# Basic_Logic_gates.net
KiCad netlist of a schematic drawn in Altium Designer
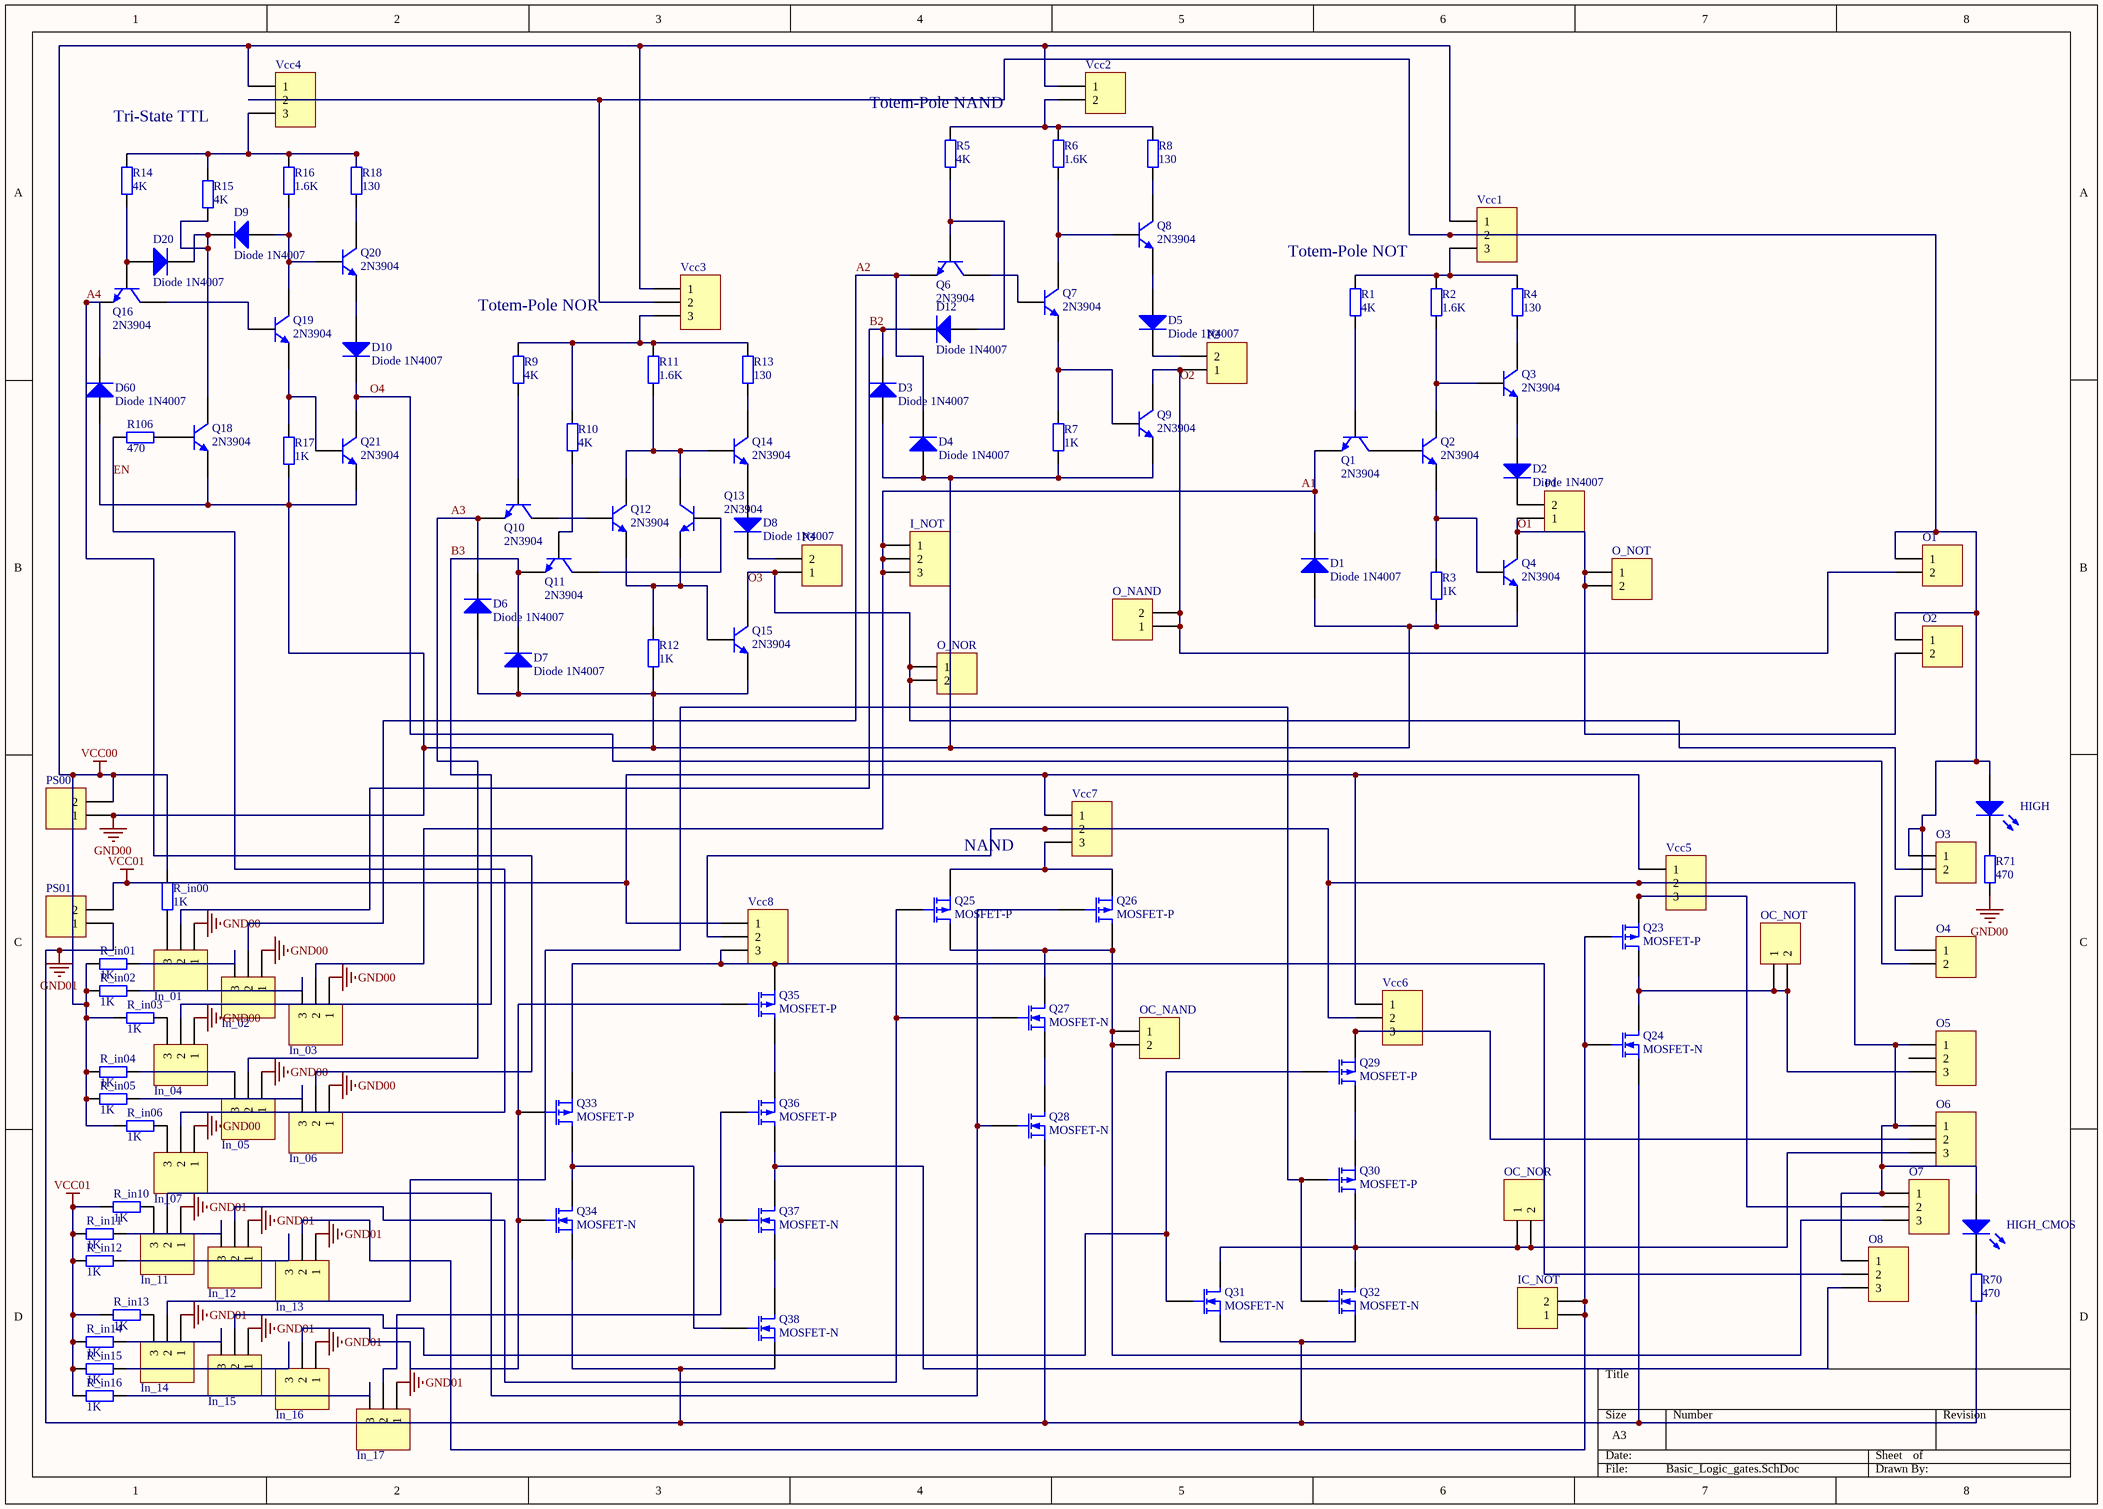
[diagram p0: Basic_Logic_gates.SchDoc]

(export (version "E")
  (design (tool "Eeschema 10.0.6"))
  (components
    (comp (ref "D1")
      (value "Diode 1N4007")
      (footprint "DO-41")
      (description "1 Amp General Purpose Rectifier")
      (libsource (lib "Miscellaneous Devices") (part "Diode 1N4007"))
    )
    (comp (ref "D2")
      (value "Diode 1N4007")
      (footprint "DO-41")
      (description "1 Amp General Purpose Rectifier")
      (libsource (lib "Miscellaneous Devices") (part "Diode 1N4007"))
    )
    (comp (ref "D3")
      (value "Diode 1N4007")
      (footprint "DO-41")
      (description "1 Amp General Purpose Rectifier")
      (libsource (lib "Miscellaneous Devices") (part "Diode 1N4007"))
    )
    (comp (ref "D4")
      (value "Diode 1N4007")
      (footprint "DO-41")
      (description "1 Amp General Purpose Rectifier")
      (libsource (lib "Miscellaneous Devices") (part "Diode 1N4007"))
    )
    (comp (ref "D5")
      (value "Diode 1N4007")
      (footprint "DO-41")
      (description "1 Amp General Purpose Rectifier")
      (libsource (lib "Miscellaneous Devices") (part "Diode 1N4007"))
    )
    (comp (ref "D6")
      (value "Diode 1N4007")
      (footprint "DO-41")
      (description "1 Amp General Purpose Rectifier")
      (libsource (lib "Miscellaneous Devices") (part "Diode 1N4007"))
    )
    (comp (ref "D7")
      (value "Diode 1N4007")
      (footprint "DO-41")
      (description "1 Amp General Purpose Rectifier")
      (libsource (lib "Miscellaneous Devices") (part "Diode 1N4007"))
    )
    (comp (ref "D8")
      (value "Diode 1N4007")
      (footprint "DO-41")
      (description "1 Amp General Purpose Rectifier")
      (libsource (lib "Miscellaneous Devices") (part "Diode 1N4007"))
    )
    (comp (ref "D9")
      (value "Diode 1N4007")
      (footprint "DO-41")
      (description "1 Amp General Purpose Rectifier")
      (libsource (lib "Miscellaneous Devices") (part "Diode 1N4007"))
    )
    (comp (ref "D10")
      (value "Diode 1N4007")
      (footprint "DO-41")
      (description "1 Amp General Purpose Rectifier")
      (libsource (lib "Miscellaneous Devices") (part "Diode 1N4007"))
    )
    (comp (ref "D12")
      (value "Diode 1N4007")
      (footprint "DO-41")
      (description "1 Amp General Purpose Rectifier")
      (libsource (lib "Miscellaneous Devices") (part "Diode 1N4007"))
    )
    (comp (ref "D20")
      (value "Diode 1N4007")
      (footprint "DO-41")
      (description "1 Amp General Purpose Rectifier")
      (libsource (lib "Miscellaneous Devices") (part "Diode 1N4007"))
    )
    (comp (ref "D60")
      (value "Diode 1N4007")
      (footprint "DO-41")
      (description "1 Amp General Purpose Rectifier")
      (libsource (lib "Miscellaneous Devices") (part "Diode 1N4007"))
    )
    (comp (ref "HIGH")
      (value "LED0")
      (footprint "LED-0")
      (description "Typical INFRARED GaAs LED")
      (libsource (lib "Miscellaneous Devices") (part "LED0"))
    )
    (comp (ref "HIGH_CMOS")
      (value "LED0")
      (footprint "LED-0")
      (description "Typical INFRARED GaAs LED")
      (libsource (lib "Miscellaneous Devices") (part "LED0"))
    )
    (comp (ref "IC_NOT")
      (value "Header 2")
      (footprint "HDR1X2")
      (description "Header, 2-Pin")
      (libsource (lib "Miscellaneous Connectors") (part "Header 2"))
    )
    (comp (ref "In_01")
      (value "Header 3")
      (footprint "HDR1X3")
      (description "Header, 3-Pin")
      (libsource (lib "") (part "Header 3_1"))
    )
    (comp (ref "In_02")
      (value "Header 3")
      (footprint "HDR1X3")
      (description "Header, 3-Pin")
      (libsource (lib "") (part "Header 3_1"))
    )
    (comp (ref "In_03")
      (value "Header 3")
      (footprint "HDR1X3")
      (description "Header, 3-Pin")
      (libsource (lib "") (part "Header 3_1"))
    )
    (comp (ref "In_04")
      (value "Header 3")
      (footprint "HDR1X3")
      (description "Header, 3-Pin")
      (libsource (lib "") (part "Header 3_1"))
    )
    (comp (ref "In_05")
      (value "Header 3")
      (footprint "HDR1X3")
      (description "Header, 3-Pin")
      (libsource (lib "") (part "Header 3_1"))
    )
    (comp (ref "In_06")
      (value "Header 3")
      (footprint "HDR1X3")
      (description "Header, 3-Pin")
      (libsource (lib "") (part "Header 3_1"))
    )
    (comp (ref "In_07")
      (value "Header 3")
      (footprint "HDR1X3")
      (description "Header, 3-Pin")
      (libsource (lib "") (part "Header 3_1"))
    )
    (comp (ref "In_11")
      (value "Header 3")
      (footprint "HDR1X3")
      (description "Header, 3-Pin")
      (libsource (lib "") (part "Header 3_1"))
    )
    (comp (ref "In_12")
      (value "Header 3")
      (footprint "HDR1X3")
      (description "Header, 3-Pin")
      (libsource (lib "") (part "Header 3_1"))
    )
    (comp (ref "In_13")
      (value "Header 3")
      (footprint "HDR1X3")
      (description "Header, 3-Pin")
      (libsource (lib "") (part "Header 3_1"))
    )
    (comp (ref "In_14")
      (value "Header 3")
      (footprint "HDR1X3")
      (description "Header, 3-Pin")
      (libsource (lib "") (part "Header 3_1"))
    )
    (comp (ref "In_15")
      (value "Header 3")
      (footprint "HDR1X3")
      (description "Header, 3-Pin")
      (libsource (lib "") (part "Header 3_1"))
    )
    (comp (ref "In_16")
      (value "Header 3")
      (footprint "HDR1X3")
      (description "Header, 3-Pin")
      (libsource (lib "") (part "Header 3_1"))
    )
    (comp (ref "In_17")
      (value "Header 3")
      (footprint "HDR1X3")
      (description "Header, 3-Pin")
      (libsource (lib "") (part "Header 3_1"))
    )
    (comp (ref "I_NOT")
      (value "Header 3")
      (footprint "HDR1X3")
      (description "Header, 3-Pin")
      (libsource (lib "Miscellaneous Connectors") (part "Header 3"))
    )
    (comp (ref "O1")
      (value "Header 2")
      (footprint "HDR1X2")
      (description "Header, 2-Pin")
      (libsource (lib "") (part "Header 2_1"))
    )
    (comp (ref "O2")
      (value "Header 2")
      (footprint "HDR1X2")
      (description "Header, 2-Pin")
      (libsource (lib "") (part "Header 2_1"))
    )
    (comp (ref "O3")
      (value "Header 2")
      (footprint "HDR1X2")
      (description "Header, 2-Pin")
      (libsource (lib "") (part "Header 2_1"))
    )
    (comp (ref "O4")
      (value "Header 2")
      (footprint "HDR1X2")
      (description "Header, 2-Pin")
      (libsource (lib "") (part "Header 2_1"))
    )
    (comp (ref "O5")
      (value "Header 3")
      (footprint "HDR1X3")
      (description "Header, 3-Pin")
      (libsource (lib "Miscellaneous Connectors") (part "Header 3"))
    )
    (comp (ref "O6")
      (value "Header 3")
      (footprint "HDR1X3")
      (description "Header, 3-Pin")
      (libsource (lib "Miscellaneous Connectors") (part "Header 3"))
    )
    (comp (ref "O7")
      (value "Header 3")
      (footprint "HDR1X3")
      (description "Header, 3-Pin")
      (libsource (lib "Miscellaneous Connectors") (part "Header 3"))
    )
    (comp (ref "O8")
      (value "Header 3")
      (footprint "HDR1X3")
      (description "Header, 3-Pin")
      (libsource (lib "Miscellaneous Connectors") (part "Header 3"))
    )
    (comp (ref "OC_NAND")
      (value "Header 2")
      (footprint "HDR1X2")
      (description "Header, 2-Pin")
      (libsource (lib "") (part "Header 2_1"))
    )
    (comp (ref "OC_NOR")
      (value "Header 2")
      (footprint "HDR1X2")
      (description "Header, 2-Pin")
      (libsource (lib "") (part "Header 2_2"))
    )
    (comp (ref "OC_NOT")
      (value "Header 2")
      (footprint "HDR1X2")
      (description "Header, 2-Pin")
      (libsource (lib "") (part "Header 2_2"))
    )
    (comp (ref "O_NAND")
      (value "Header 2")
      (footprint "HDR1X2")
      (description "Header, 2-Pin")
      (libsource (lib "Miscellaneous Connectors") (part "Header 2"))
    )
    (comp (ref "O_NOR")
      (value "Header 2")
      (footprint "HDR1X2")
      (description "Header, 2-Pin")
      (libsource (lib "") (part "Header 2_1"))
    )
    (comp (ref "O_NOT")
      (value "Header 2")
      (footprint "HDR1X2")
      (description "Header, 2-Pin")
      (libsource (lib "") (part "Header 2_1"))
    )
    (comp (ref "P1")
      (value "Header 2")
      (footprint "HDR1X2")
      (description "Header, 2-Pin")
      (libsource (lib "") (part "Header 2_2"))
    )
    (comp (ref "P2")
      (value "Header 2")
      (footprint "HDR1X2")
      (description "Header, 2-Pin")
      (libsource (lib "") (part "Header 2_2"))
    )
    (comp (ref "P3")
      (value "Header 2")
      (footprint "HDR1X2")
      (description "Header, 2-Pin")
      (libsource (lib "") (part "Header 2_2"))
    )
    (comp (ref "PS00")
      (value "Header 2")
      (footprint "HDR1X2")
      (description "Header, 2-Pin")
      (libsource (lib "Miscellaneous Connectors") (part "Header 2"))
    )
    (comp (ref "PS01")
      (value "Header 2")
      (footprint "HDR1X2")
      (description "Header, 2-Pin")
      (libsource (lib "Miscellaneous Connectors") (part "Header 2"))
    )
    (comp (ref "Q1")
      (value "2N3904")
      (footprint "TO-92A")
      (description "NPN General Purpose Amplifier")
      (libsource (lib "Miscellaneous Devices") (part "2N3904"))
    )
    (comp (ref "Q2")
      (value "2N3904")
      (footprint "TO-92A")
      (description "NPN General Purpose Amplifier")
      (libsource (lib "Miscellaneous Devices") (part "2N3904"))
    )
    (comp (ref "Q3")
      (value "2N3904")
      (footprint "TO-92A")
      (description "NPN General Purpose Amplifier")
      (libsource (lib "Miscellaneous Devices") (part "2N3904"))
    )
    (comp (ref "Q4")
      (value "2N3904")
      (footprint "TO-92A")
      (description "NPN General Purpose Amplifier")
      (libsource (lib "Miscellaneous Devices") (part "2N3904"))
    )
    (comp (ref "Q6")
      (value "2N3904")
      (footprint "TO-92A")
      (description "NPN General Purpose Amplifier")
      (libsource (lib "Miscellaneous Devices") (part "2N3904"))
    )
    (comp (ref "Q7")
      (value "2N3904")
      (footprint "TO-92A")
      (description "NPN General Purpose Amplifier")
      (libsource (lib "Miscellaneous Devices") (part "2N3904"))
    )
    (comp (ref "Q8")
      (value "2N3904")
      (footprint "TO-92A")
      (description "NPN General Purpose Amplifier")
      (libsource (lib "Miscellaneous Devices") (part "2N3904"))
    )
    (comp (ref "Q9")
      (value "2N3904")
      (footprint "TO-92A")
      (description "NPN General Purpose Amplifier")
      (libsource (lib "Miscellaneous Devices") (part "2N3904"))
    )
    (comp (ref "Q10")
      (value "2N3904")
      (footprint "TO-92A")
      (description "NPN General Purpose Amplifier")
      (libsource (lib "Miscellaneous Devices") (part "2N3904"))
    )
    (comp (ref "Q11")
      (value "2N3904")
      (footprint "TO-92A")
      (description "NPN General Purpose Amplifier")
      (libsource (lib "Miscellaneous Devices") (part "2N3904"))
    )
    (comp (ref "Q12")
      (value "2N3904")
      (footprint "TO-92A")
      (description "NPN General Purpose Amplifier")
      (libsource (lib "Miscellaneous Devices") (part "2N3904"))
    )
    (comp (ref "Q13")
      (value "2N3904")
      (footprint "TO-92A")
      (description "NPN General Purpose Amplifier")
      (libsource (lib "Miscellaneous Devices") (part "2N3904"))
    )
    (comp (ref "Q14")
      (value "2N3904")
      (footprint "TO-92A")
      (description "NPN General Purpose Amplifier")
      (libsource (lib "Miscellaneous Devices") (part "2N3904"))
    )
    (comp (ref "Q15")
      (value "2N3904")
      (footprint "TO-92A")
      (description "NPN General Purpose Amplifier")
      (libsource (lib "Miscellaneous Devices") (part "2N3904"))
    )
    (comp (ref "Q16")
      (value "2N3904")
      (footprint "TO-92A")
      (description "NPN General Purpose Amplifier")
      (libsource (lib "Miscellaneous Devices") (part "2N3904"))
    )
    (comp (ref "Q18")
      (value "2N3904")
      (footprint "TO-92A")
      (description "NPN General Purpose Amplifier")
      (libsource (lib "Miscellaneous Devices") (part "2N3904"))
    )
    (comp (ref "Q19")
      (value "2N3904")
      (footprint "TO-92A")
      (description "NPN General Purpose Amplifier")
      (libsource (lib "Miscellaneous Devices") (part "2N3904"))
    )
    (comp (ref "Q20")
      (value "2N3904")
      (footprint "TO-92A")
      (description "NPN General Purpose Amplifier")
      (libsource (lib "Miscellaneous Devices") (part "2N3904"))
    )
    (comp (ref "Q21")
      (value "2N3904")
      (footprint "TO-92A")
      (description "NPN General Purpose Amplifier")
      (libsource (lib "Miscellaneous Devices") (part "2N3904"))
    )
    (comp (ref "Q23")
      (value "MOSFET-P")
      (footprint "E3")
      (description "P-Channel MOSFET")
      (libsource (lib "Miscellaneous Devices") (part "MOSFET-P"))
    )
    (comp (ref "Q24")
      (value "MOSFET-N")
      (footprint "E3")
      (description "N-Channel MOSFET")
      (libsource (lib "Miscellaneous Devices") (part "MOSFET-N"))
    )
    (comp (ref "Q25")
      (value "MOSFET-P")
      (footprint "E3")
      (description "P-Channel MOSFET")
      (libsource (lib "Miscellaneous Devices") (part "MOSFET-P"))
    )
    (comp (ref "Q26")
      (value "MOSFET-P")
      (footprint "E3")
      (description "P-Channel MOSFET")
      (libsource (lib "Miscellaneous Devices") (part "MOSFET-P"))
    )
    (comp (ref "Q27")
      (value "MOSFET-N")
      (footprint "E3")
      (description "N-Channel MOSFET")
      (libsource (lib "Miscellaneous Devices") (part "MOSFET-N"))
    )
    (comp (ref "Q28")
      (value "MOSFET-N")
      (footprint "E3")
      (description "N-Channel MOSFET")
      (libsource (lib "Miscellaneous Devices") (part "MOSFET-N"))
    )
    (comp (ref "Q29")
      (value "MOSFET-P")
      (footprint "E3")
      (description "P-Channel MOSFET")
      (libsource (lib "Miscellaneous Devices") (part "MOSFET-P"))
    )
    (comp (ref "Q30")
      (value "MOSFET-P")
      (footprint "E3")
      (description "P-Channel MOSFET")
      (libsource (lib "Miscellaneous Devices") (part "MOSFET-P"))
    )
    (comp (ref "Q31")
      (value "MOSFET-N")
      (footprint "E3")
      (description "N-Channel MOSFET")
      (libsource (lib "Miscellaneous Devices") (part "MOSFET-N"))
    )
    (comp (ref "Q32")
      (value "MOSFET-N")
      (footprint "E3")
      (description "N-Channel MOSFET")
      (libsource (lib "Miscellaneous Devices") (part "MOSFET-N"))
    )
    (comp (ref "Q33")
      (value "MOSFET-P")
      (footprint "E3")
      (description "P-Channel MOSFET")
      (libsource (lib "Miscellaneous Devices") (part "MOSFET-P"))
    )
    (comp (ref "Q34")
      (value "MOSFET-N")
      (footprint "E3")
      (description "N-Channel MOSFET")
      (libsource (lib "Miscellaneous Devices") (part "MOSFET-N"))
    )
    (comp (ref "Q35")
      (value "MOSFET-P")
      (footprint "E3")
      (description "P-Channel MOSFET")
      (libsource (lib "Miscellaneous Devices") (part "MOSFET-P"))
    )
    (comp (ref "Q36")
      (value "MOSFET-P")
      (footprint "E3")
      (description "P-Channel MOSFET")
      (libsource (lib "Miscellaneous Devices") (part "MOSFET-P"))
    )
    (comp (ref "Q37")
      (value "MOSFET-N")
      (footprint "E3")
      (description "N-Channel MOSFET")
      (libsource (lib "Miscellaneous Devices") (part "MOSFET-N"))
    )
    (comp (ref "Q38")
      (value "MOSFET-N")
      (footprint "E3")
      (description "N-Channel MOSFET")
      (libsource (lib "Miscellaneous Devices") (part "MOSFET-N"))
    )
    (comp (ref "R1")
      (value "4K")
      (footprint "AXIAL-0.4")
      (description "Resistor")
      (libsource (lib "Miscellaneous Devices") (part "Res2"))
    )
    (comp (ref "R2")
      (value "1.6K")
      (footprint "AXIAL-0.4")
      (description "Resistor")
      (libsource (lib "Miscellaneous Devices") (part "Res2"))
    )
    (comp (ref "R3")
      (value "1K")
      (footprint "AXIAL-0.4")
      (description "Resistor")
      (libsource (lib "Miscellaneous Devices") (part "Res2"))
    )
    (comp (ref "R4")
      (value "130")
      (footprint "AXIAL-0.4")
      (description "Resistor")
      (libsource (lib "Miscellaneous Devices") (part "Res2"))
    )
    (comp (ref "R5")
      (value "4K")
      (footprint "AXIAL-0.4")
      (description "Resistor")
      (libsource (lib "Miscellaneous Devices") (part "Res2"))
    )
    (comp (ref "R6")
      (value "1.6K")
      (footprint "AXIAL-0.4")
      (description "Resistor")
      (libsource (lib "Miscellaneous Devices") (part "Res2"))
    )
    (comp (ref "R7")
      (value "1K")
      (footprint "AXIAL-0.4")
      (description "Resistor")
      (libsource (lib "Miscellaneous Devices") (part "Res2"))
    )
    (comp (ref "R8")
      (value "130")
      (footprint "AXIAL-0.4")
      (description "Resistor")
      (libsource (lib "Miscellaneous Devices") (part "Res2"))
    )
    (comp (ref "R9")
      (value "4K")
      (footprint "AXIAL-0.4")
      (description "Resistor")
      (libsource (lib "Miscellaneous Devices") (part "Res2"))
    )
    (comp (ref "R10")
      (value "4K")
      (footprint "AXIAL-0.4")
      (description "Resistor")
      (libsource (lib "Miscellaneous Devices") (part "Res2"))
    )
    (comp (ref "R11")
      (value "1.6K")
      (footprint "AXIAL-0.4")
      (description "Resistor")
      (libsource (lib "Miscellaneous Devices") (part "Res2"))
    )
    (comp (ref "R12")
      (value "1K")
      (footprint "AXIAL-0.4")
      (description "Resistor")
      (libsource (lib "Miscellaneous Devices") (part "Res2"))
    )
    (comp (ref "R13")
      (value "130")
      (footprint "AXIAL-0.4")
      (description "Resistor")
      (libsource (lib "Miscellaneous Devices") (part "Res2"))
    )
    (comp (ref "R14")
      (value "4K")
      (footprint "AXIAL-0.4")
      (description "Resistor")
      (libsource (lib "Miscellaneous Devices") (part "Res2"))
    )
    (comp (ref "R15")
      (value "4K")
      (footprint "AXIAL-0.4")
      (description "Resistor")
      (libsource (lib "Miscellaneous Devices") (part "Res2"))
    )
    (comp (ref "R16")
      (value "1.6K")
      (footprint "AXIAL-0.4")
      (description "Resistor")
      (libsource (lib "Miscellaneous Devices") (part "Res2"))
    )
    (comp (ref "R17")
      (value "1K")
      (footprint "AXIAL-0.4")
      (description "Resistor")
      (libsource (lib "Miscellaneous Devices") (part "Res2"))
    )
    (comp (ref "R18")
      (value "130")
      (footprint "AXIAL-0.4")
      (description "Resistor")
      (libsource (lib "Miscellaneous Devices") (part "Res2"))
    )
    (comp (ref "R70")
      (value "470")
      (footprint "AXIAL-0.4")
      (description "Resistor")
      (libsource (lib "Miscellaneous Devices") (part "Res2"))
    )
    (comp (ref "R71")
      (value "470")
      (footprint "AXIAL-0.4")
      (description "Resistor")
      (libsource (lib "Miscellaneous Devices") (part "Res2"))
    )
    (comp (ref "R106")
      (value "470")
      (footprint "AXIAL-0.4")
      (description "Resistor")
      (libsource (lib "") (part "Res2_2"))
    )
    (comp (ref "R_in00")
      (value "1K")
      (footprint "AXIAL-0.4")
      (description "Resistor")
      (libsource (lib "") (part "Res2_3"))
    )
    (comp (ref "R_in01")
      (value "1K")
      (footprint "AXIAL-0.4")
      (description "Resistor")
      (libsource (lib "") (part "Res2_1"))
    )
    (comp (ref "R_in02")
      (value "1K")
      (footprint "AXIAL-0.4")
      (description "Resistor")
      (libsource (lib "") (part "Res2_1"))
    )
    (comp (ref "R_in03")
      (value "1K")
      (footprint "AXIAL-0.4")
      (description "Resistor")
      (libsource (lib "") (part "Res2_1"))
    )
    (comp (ref "R_in04")
      (value "1K")
      (footprint "AXIAL-0.4")
      (description "Resistor")
      (libsource (lib "") (part "Res2_1"))
    )
    (comp (ref "R_in05")
      (value "1K")
      (footprint "AXIAL-0.4")
      (description "Resistor")
      (libsource (lib "") (part "Res2_1"))
    )
    (comp (ref "R_in06")
      (value "1K")
      (footprint "AXIAL-0.4")
      (description "Resistor")
      (libsource (lib "") (part "Res2_1"))
    )
    (comp (ref "R_in10")
      (value "1K")
      (footprint "AXIAL-0.4")
      (description "Resistor")
      (libsource (lib "") (part "Res2_1"))
    )
    (comp (ref "R_in11")
      (value "1K")
      (footprint "AXIAL-0.4")
      (description "Resistor")
      (libsource (lib "") (part "Res2_1"))
    )
    (comp (ref "R_in12")
      (value "1K")
      (footprint "AXIAL-0.4")
      (description "Resistor")
      (libsource (lib "") (part "Res2_1"))
    )
    (comp (ref "R_in13")
      (value "1K")
      (footprint "AXIAL-0.4")
      (description "Resistor")
      (libsource (lib "") (part "Res2_1"))
    )
    (comp (ref "R_in14")
      (value "1K")
      (footprint "AXIAL-0.4")
      (description "Resistor")
      (libsource (lib "") (part "Res2_1"))
    )
    (comp (ref "R_in15")
      (value "1K")
      (footprint "AXIAL-0.4")
      (description "Resistor")
      (libsource (lib "") (part "Res2_1"))
    )
    (comp (ref "R_in16")
      (value "1K")
      (footprint "AXIAL-0.4")
      (description "Resistor")
      (libsource (lib "") (part "Res2_1"))
    )
    (comp (ref "Vcc1")
      (value "Header 3")
      (footprint "HDR1X3")
      (description "Header, 3-Pin")
      (libsource (lib "Miscellaneous Connectors") (part "Header 3"))
    )
    (comp (ref "Vcc2")
      (value "Header 2")
      (footprint "HDR1X2")
      (description "Header, 2-Pin")
      (libsource (lib "") (part "Header 2_1"))
    )
    (comp (ref "Vcc3")
      (value "Header 3")
      (footprint "HDR1X3")
      (description "Header, 3-Pin")
      (libsource (lib "Miscellaneous Connectors") (part "Header 3"))
    )
    (comp (ref "Vcc4")
      (value "Header 3")
      (footprint "HDR1X3")
      (description "Header, 3-Pin")
      (libsource (lib "Miscellaneous Connectors") (part "Header 3"))
    )
    (comp (ref "Vcc5")
      (value "Header 3")
      (footprint "HDR1X3")
      (description "Header, 3-Pin")
      (libsource (lib "Miscellaneous Connectors") (part "Header 3"))
    )
    (comp (ref "Vcc6")
      (value "Header 3")
      (footprint "HDR1X3")
      (description "Header, 3-Pin")
      (libsource (lib "Miscellaneous Connectors") (part "Header 3"))
    )
    (comp (ref "Vcc7")
      (value "Header 3")
      (footprint "HDR1X3")
      (description "Header, 3-Pin")
      (libsource (lib "Miscellaneous Connectors") (part "Header 3"))
    )
    (comp (ref "Vcc8")
      (value "Header 3")
      (footprint "HDR1X3")
      (description "Header, 3-Pin")
      (libsource (lib "Miscellaneous Connectors") (part "Header 3"))
    )
  )
  (nets
    (net (code "1") (name "/A1") (class "Default")
      (node (ref "D1") (pin "2") (pinfunction "K_2") (pintype "passive"))
      (node (ref "I_NOT") (pin "1") (pinfunction "1_1") (pintype "passive"))
      (node (ref "I_NOT") (pin "2") (pinfunction "2_2") (pintype "passive"))
      (node (ref "I_NOT") (pin "3") (pinfunction "3_3") (pintype "passive"))
      (node (ref "In_03") (pin "2") (pinfunction "2_2") (pintype "passive"))
      (node (ref "Q1") (pin "1") (pinfunction "E_1") (pintype "passive"))
    )
    (net (code "2") (name "/A2") (class "Default")
      (node (ref "D4") (pin "2") (pinfunction "K_2") (pintype "passive"))
      (node (ref "In_02") (pin "2") (pinfunction "2_2") (pintype "passive"))
      (node (ref "Q6") (pin "1") (pinfunction "E_1") (pintype "passive"))
    )
    (net (code "3") (name "/A3") (class "Default")
      (node (ref "D6") (pin "2") (pinfunction "K_2") (pintype "passive"))
      (node (ref "In_05") (pin "2") (pinfunction "2_2") (pintype "passive"))
      (node (ref "Q10") (pin "1") (pinfunction "E_1") (pintype "passive"))
    )
    (net (code "4") (name "/A4") (class "Default")
      (node (ref "D60") (pin "2") (pinfunction "K_2") (pintype "passive"))
      (node (ref "In_06") (pin "2") (pinfunction "2_2") (pintype "passive"))
      (node (ref "Q16") (pin "1") (pinfunction "E_1") (pintype "passive"))
    )
    (net (code "5") (name "/B2") (class "Default")
      (node (ref "D12") (pin "2") (pinfunction "K_2") (pintype "passive"))
      (node (ref "D3") (pin "2") (pinfunction "K_2") (pintype "passive"))
      (node (ref "In_01") (pin "2") (pinfunction "2_2") (pintype "passive"))
    )
    (net (code "6") (name "/B3") (class "Default")
      (node (ref "D7") (pin "2") (pinfunction "K_2") (pintype "passive"))
      (node (ref "In_04") (pin "2") (pinfunction "2_2") (pintype "passive"))
      (node (ref "Q11") (pin "1") (pinfunction "E_1") (pintype "passive"))
    )
    (net (code "7") (name "/EN") (class "Default")
      (node (ref "In_07") (pin "2") (pinfunction "2_2") (pintype "passive"))
      (node (ref "R106") (pin "2") (pinfunction "2_2") (pintype "passive"))
    )
    (net (code "8") (name "/O1") (class "Default")
      (node (ref "O2") (pin "2") (pinfunction "2_2") (pintype "passive"))
      (node (ref "O_NOT") (pin "1") (pinfunction "1_1") (pintype "passive"))
      (node (ref "O_NOT") (pin "2") (pinfunction "2_2") (pintype "passive"))
      (node (ref "P1") (pin "1") (pinfunction "1_1") (pintype "passive"))
      (node (ref "Q4") (pin "3") (pinfunction "C_3") (pintype "passive"))
    )
    (net (code "9") (name "/O2") (class "Default")
      (node (ref "O1") (pin "2") (pinfunction "2_2") (pintype "passive"))
      (node (ref "O_NAND") (pin "1") (pinfunction "1_1") (pintype "passive"))
      (node (ref "O_NAND") (pin "2") (pinfunction "2_2") (pintype "passive"))
      (node (ref "P2") (pin "1") (pinfunction "1_1") (pintype "passive"))
      (node (ref "Q9") (pin "3") (pinfunction "C_3") (pintype "passive"))
    )
    (net (code "10") (name "/O3") (class "Default")
      (node (ref "O3") (pin "2") (pinfunction "2_2") (pintype "passive"))
      (node (ref "O_NOR") (pin "1") (pinfunction "1_1") (pintype "passive"))
      (node (ref "O_NOR") (pin "2") (pinfunction "2_2") (pintype "passive"))
      (node (ref "P3") (pin "1") (pinfunction "1_1") (pintype "passive"))
      (node (ref "Q15") (pin "3") (pinfunction "C_3") (pintype "passive"))
    )
    (net (code "11") (name "/O4") (class "Default")
      (node (ref "D10") (pin "2") (pinfunction "K_2") (pintype "passive"))
      (node (ref "O4") (pin "2") (pinfunction "2_2") (pintype "passive"))
      (node (ref "Q21") (pin "3") (pinfunction "C_3") (pintype "passive"))
    )
    (net (code "12") (name "GND00") (class "Default")
      (node (ref "D1") (pin "1") (pinfunction "A_1") (pintype "passive"))
      (node (ref "D3") (pin "1") (pinfunction "A_1") (pintype "passive"))
      (node (ref "D4") (pin "1") (pinfunction "A_1") (pintype "passive"))
      (node (ref "D6") (pin "1") (pinfunction "A_1") (pintype "passive"))
      (node (ref "D60") (pin "1") (pinfunction "A_1") (pintype "passive"))
      (node (ref "D7") (pin "1") (pinfunction "A_1") (pintype "passive"))
      (node (ref "In_01") (pin "1") (pinfunction "1_1") (pintype "passive"))
      (node (ref "In_02") (pin "1") (pinfunction "1_1") (pintype "passive"))
      (node (ref "In_03") (pin "1") (pinfunction "1_1") (pintype "passive"))
      (node (ref "In_04") (pin "1") (pinfunction "1_1") (pintype "passive"))
      (node (ref "In_05") (pin "1") (pinfunction "1_1") (pintype "passive"))
      (node (ref "In_06") (pin "1") (pinfunction "1_1") (pintype "passive"))
      (node (ref "In_07") (pin "1") (pinfunction "1_1") (pintype "passive"))
      (node (ref "PS00") (pin "1") (pinfunction "1_1") (pintype "passive"))
      (node (ref "Q15") (pin "1") (pinfunction "E_1") (pintype "passive"))
      (node (ref "Q18") (pin "1") (pinfunction "E_1") (pintype "passive"))
      (node (ref "Q21") (pin "1") (pinfunction "E_1") (pintype "passive"))
      (node (ref "Q4") (pin "1") (pinfunction "E_1") (pintype "passive"))
      (node (ref "Q9") (pin "1") (pinfunction "E_1") (pintype "passive"))
      (node (ref "R12") (pin "1") (pinfunction "1_1") (pintype "passive"))
      (node (ref "R17") (pin "1") (pinfunction "1_1") (pintype "passive"))
      (node (ref "R3") (pin "1") (pinfunction "1_1") (pintype "passive"))
      (node (ref "R7") (pin "1") (pinfunction "1_1") (pintype "passive"))
      (node (ref "R71") (pin "1") (pinfunction "1_1") (pintype "passive"))
    )
    (net (code "13") (name "GND01") (class "Default")
      (node (ref "In_11") (pin "1") (pinfunction "1_1") (pintype "passive"))
      (node (ref "In_12") (pin "1") (pinfunction "1_1") (pintype "passive"))
      (node (ref "In_13") (pin "1") (pinfunction "1_1") (pintype "passive"))
      (node (ref "In_14") (pin "1") (pinfunction "1_1") (pintype "passive"))
      (node (ref "In_15") (pin "1") (pinfunction "1_1") (pintype "passive"))
      (node (ref "In_16") (pin "1") (pinfunction "1_1") (pintype "passive"))
      (node (ref "In_17") (pin "1") (pinfunction "1_1") (pintype "passive"))
      (node (ref "PS01") (pin "1") (pinfunction "1_1") (pintype "passive"))
      (node (ref "Q24") (pin "3") (pinfunction "S_3") (pintype "passive"))
      (node (ref "Q28") (pin "3") (pinfunction "S_3") (pintype "passive"))
      (node (ref "Q31") (pin "3") (pinfunction "S_3") (pintype "passive"))
      (node (ref "Q32") (pin "3") (pinfunction "S_3") (pintype "passive"))
      (node (ref "Q34") (pin "3") (pinfunction "S_3") (pintype "passive"))
      (node (ref "Q38") (pin "3") (pinfunction "S_3") (pintype "passive"))
      (node (ref "R70") (pin "1") (pinfunction "1_1") (pintype "passive"))
    )
    (net (code "14") (name "Net-(D2-A)") (class "Default")
      (node (ref "D2") (pin "1") (pinfunction "A_1") (pintype "passive"))
      (node (ref "Q3") (pin "1") (pinfunction "E_1") (pintype "passive"))
    )
    (net (code "15") (name "Net-(D2-K)") (class "Default")
      (node (ref "D2") (pin "2") (pinfunction "K_2") (pintype "passive"))
      (node (ref "P1") (pin "2") (pinfunction "2_2") (pintype "passive"))
    )
    (net (code "16") (name "Net-(D5-A)") (class "Default")
      (node (ref "D5") (pin "1") (pinfunction "A_1") (pintype "passive"))
      (node (ref "Q8") (pin "1") (pinfunction "E_1") (pintype "passive"))
    )
    (net (code "17") (name "Net-(D5-K)") (class "Default")
      (node (ref "D5") (pin "2") (pinfunction "K_2") (pintype "passive"))
      (node (ref "P2") (pin "2") (pinfunction "2_2") (pintype "passive"))
    )
    (net (code "18") (name "Net-(D8-A)") (class "Default")
      (node (ref "D8") (pin "1") (pinfunction "A_1") (pintype "passive"))
      (node (ref "Q14") (pin "1") (pinfunction "E_1") (pintype "passive"))
    )
    (net (code "19") (name "Net-(D8-K)") (class "Default")
      (node (ref "D8") (pin "2") (pinfunction "K_2") (pintype "passive"))
      (node (ref "P3") (pin "2") (pinfunction "2_2") (pintype "passive"))
    )
    (net (code "20") (name "Net-(D9-A)") (class "Default")
      (node (ref "D9") (pin "1") (pinfunction "A_1") (pintype "passive"))
      (node (ref "Q19") (pin "3") (pinfunction "C_3") (pintype "passive"))
      (node (ref "Q20") (pin "2") (pinfunction "B_2") (pintype "passive"))
      (node (ref "R16") (pin "1") (pinfunction "1_1") (pintype "passive"))
    )
    (net (code "21") (name "Net-(D10-A)") (class "Default")
      (node (ref "D10") (pin "1") (pinfunction "A_1") (pintype "passive"))
      (node (ref "Q20") (pin "1") (pinfunction "E_1") (pintype "passive"))
    )
    (net (code "22") (name "Net-(D12-A)") (class "Default")
      (node (ref "D12") (pin "1") (pinfunction "A_1") (pintype "passive"))
      (node (ref "Q6") (pin "2") (pinfunction "B_2") (pintype "passive"))
      (node (ref "R5") (pin "1") (pinfunction "1_1") (pintype "passive"))
    )
    (net (code "23") (name "Net-(D20-A)") (class "Default")
      (node (ref "D20") (pin "1") (pinfunction "A_1") (pintype "passive"))
      (node (ref "Q16") (pin "2") (pinfunction "B_2") (pintype "passive"))
      (node (ref "R14") (pin "1") (pinfunction "1_1") (pintype "passive"))
    )
    (net (code "24") (name "Net-(D20-K)") (class "Default")
      (node (ref "D20") (pin "2") (pinfunction "K_2") (pintype "passive"))
      (node (ref "D9") (pin "2") (pinfunction "K_2") (pintype "passive"))
      (node (ref "Q18") (pin "3") (pinfunction "C_3") (pintype "passive"))
      (node (ref "R15") (pin "1") (pinfunction "1_1") (pintype "passive"))
    )
    (net (code "25") (name "Net-(HIGH-A)") (class "Default")
      (node (ref "HIGH") (pin "1") (pinfunction "A_1") (pintype "passive"))
      (node (ref "O1") (pin "1") (pinfunction "1_1") (pintype "passive"))
      (node (ref "O2") (pin "1") (pinfunction "1_1") (pintype "passive"))
      (node (ref "O3") (pin "1") (pinfunction "1_1") (pintype "passive"))
      (node (ref "O4") (pin "1") (pinfunction "1_1") (pintype "passive"))
      (node (ref "Vcc1") (pin "2") (pinfunction "2_2") (pintype "passive"))
      (node (ref "Vcc3") (pin "2") (pinfunction "2_2") (pintype "passive"))
      (node (ref "Vcc4") (pin "2") (pinfunction "2_2") (pintype "passive"))
    )
    (net (code "26") (name "Net-(HIGH-K)") (class "Default")
      (node (ref "HIGH") (pin "2") (pinfunction "K_2") (pintype "passive"))
      (node (ref "R71") (pin "2") (pinfunction "2_2") (pintype "passive"))
    )
    (net (code "27") (name "Net-(HIGH_CMOS-A)") (class "Default")
      (node (ref "HIGH_CMOS") (pin "1") (pinfunction "A_1") (pintype "passive"))
      (node (ref "O5") (pin "1") (pinfunction "1_1") (pintype "passive"))
      (node (ref "O6") (pin "1") (pinfunction "1_1") (pintype "passive"))
      (node (ref "O7") (pin "1") (pinfunction "1_1") (pintype "passive"))
      (node (ref "O8") (pin "1") (pinfunction "1_1") (pintype "passive"))
      (node (ref "Vcc5") (pin "2") (pinfunction "2_2") (pintype "passive"))
      (node (ref "Vcc6") (pin "2") (pinfunction "2_2") (pintype "passive"))
      (node (ref "Vcc7") (pin "2") (pinfunction "2_2") (pintype "passive"))
      (node (ref "Vcc8") (pin "2") (pinfunction "2_2") (pintype "passive"))
    )
    (net (code "28") (name "Net-(HIGH_CMOS-K)") (class "Default")
      (node (ref "HIGH_CMOS") (pin "2") (pinfunction "K_2") (pintype "passive"))
      (node (ref "R70") (pin "2") (pinfunction "2_2") (pintype "passive"))
    )
    (net (code "29") (name "Net-(In_01-Pad3)") (class "Default")
      (node (ref "In_01") (pin "3") (pinfunction "3_3") (pintype "passive"))
      (node (ref "R_in00") (pin "2") (pinfunction "2_2") (pintype "passive"))
    )
    (net (code "30") (name "Net-(In_02-Pad3)") (class "Default")
      (node (ref "In_02") (pin "3") (pinfunction "3_3") (pintype "passive"))
      (node (ref "R_in01") (pin "2") (pinfunction "2_2") (pintype "passive"))
    )
    (net (code "31") (name "Net-(In_03-Pad3)") (class "Default")
      (node (ref "In_03") (pin "3") (pinfunction "3_3") (pintype "passive"))
      (node (ref "R_in02") (pin "2") (pinfunction "2_2") (pintype "passive"))
    )
    (net (code "32") (name "Net-(In_04-Pad3)") (class "Default")
      (node (ref "In_04") (pin "3") (pinfunction "3_3") (pintype "passive"))
      (node (ref "R_in03") (pin "2") (pinfunction "2_2") (pintype "passive"))
    )
    (net (code "33") (name "Net-(In_05-Pad3)") (class "Default")
      (node (ref "In_05") (pin "3") (pinfunction "3_3") (pintype "passive"))
      (node (ref "R_in04") (pin "2") (pinfunction "2_2") (pintype "passive"))
    )
    (net (code "34") (name "Net-(In_06-Pad3)") (class "Default")
      (node (ref "In_06") (pin "3") (pinfunction "3_3") (pintype "passive"))
      (node (ref "R_in05") (pin "2") (pinfunction "2_2") (pintype "passive"))
    )
    (net (code "35") (name "Net-(In_07-Pad3)") (class "Default")
      (node (ref "In_07") (pin "3") (pinfunction "3_3") (pintype "passive"))
      (node (ref "R_in06") (pin "2") (pinfunction "2_2") (pintype "passive"))
    )
    (net (code "36") (name "Net-(In_11-Pad3)") (class "Default")
      (node (ref "In_11") (pin "3") (pinfunction "3_3") (pintype "passive"))
      (node (ref "R_in10") (pin "2") (pinfunction "2_2") (pintype "passive"))
    )
    (net (code "37") (name "Net-(In_12-Pad3)") (class "Default")
      (node (ref "In_12") (pin "3") (pinfunction "3_3") (pintype "passive"))
      (node (ref "R_in11") (pin "2") (pinfunction "2_2") (pintype "passive"))
    )
    (net (code "38") (name "Net-(In_13-Pad3)") (class "Default")
      (node (ref "In_13") (pin "3") (pinfunction "3_3") (pintype "passive"))
      (node (ref "R_in12") (pin "2") (pinfunction "2_2") (pintype "passive"))
    )
    (net (code "39") (name "Net-(In_14-Pad3)") (class "Default")
      (node (ref "In_14") (pin "3") (pinfunction "3_3") (pintype "passive"))
      (node (ref "R_in13") (pin "2") (pinfunction "2_2") (pintype "passive"))
    )
    (net (code "40") (name "Net-(In_15-Pad3)") (class "Default")
      (node (ref "In_15") (pin "3") (pinfunction "3_3") (pintype "passive"))
      (node (ref "R_in14") (pin "2") (pinfunction "2_2") (pintype "passive"))
    )
    (net (code "41") (name "Net-(In_16-Pad3)") (class "Default")
      (node (ref "In_16") (pin "3") (pinfunction "3_3") (pintype "passive"))
      (node (ref "R_in15") (pin "2") (pinfunction "2_2") (pintype "passive"))
    )
    (net (code "42") (name "Net-(In_17-Pad3)") (class "Default")
      (node (ref "In_17") (pin "3") (pinfunction "3_3") (pintype "passive"))
      (node (ref "R_in16") (pin "2") (pinfunction "2_2") (pintype "passive"))
    )
    (net (code "43") (name "Net-(Q1-B)") (class "Default")
      (node (ref "Q1") (pin "2") (pinfunction "B_2") (pintype "passive"))
      (node (ref "R1") (pin "1") (pinfunction "1_1") (pintype "passive"))
    )
    (net (code "44") (name "Net-(Q1-C)") (class "Default")
      (node (ref "Q1") (pin "3") (pinfunction "C_3") (pintype "passive"))
      (node (ref "Q2") (pin "2") (pinfunction "B_2") (pintype "passive"))
    )
    (net (code "45") (name "Net-(Q2-C)") (class "Default")
      (node (ref "Q2") (pin "3") (pinfunction "C_3") (pintype "passive"))
      (node (ref "Q3") (pin "2") (pinfunction "B_2") (pintype "passive"))
      (node (ref "R2") (pin "1") (pinfunction "1_1") (pintype "passive"))
    )
    (net (code "46") (name "Net-(Q2-E)") (class "Default")
      (node (ref "Q2") (pin "1") (pinfunction "E_1") (pintype "passive"))
      (node (ref "Q4") (pin "2") (pinfunction "B_2") (pintype "passive"))
      (node (ref "R3") (pin "2") (pinfunction "2_2") (pintype "passive"))
    )
    (net (code "47") (name "Net-(Q3-C)") (class "Default")
      (node (ref "Q3") (pin "3") (pinfunction "C_3") (pintype "passive"))
      (node (ref "R4") (pin "1") (pinfunction "1_1") (pintype "passive"))
    )
    (net (code "48") (name "Net-(Q6-C)") (class "Default")
      (node (ref "Q6") (pin "3") (pinfunction "C_3") (pintype "passive"))
      (node (ref "Q7") (pin "2") (pinfunction "B_2") (pintype "passive"))
    )
    (net (code "49") (name "Net-(Q7-C)") (class "Default")
      (node (ref "Q7") (pin "3") (pinfunction "C_3") (pintype "passive"))
      (node (ref "Q8") (pin "2") (pinfunction "B_2") (pintype "passive"))
      (node (ref "R6") (pin "1") (pinfunction "1_1") (pintype "passive"))
    )
    (net (code "50") (name "Net-(Q7-E)") (class "Default")
      (node (ref "Q7") (pin "1") (pinfunction "E_1") (pintype "passive"))
      (node (ref "Q9") (pin "2") (pinfunction "B_2") (pintype "passive"))
      (node (ref "R7") (pin "2") (pinfunction "2_2") (pintype "passive"))
    )
    (net (code "51") (name "Net-(Q8-C)") (class "Default")
      (node (ref "Q8") (pin "3") (pinfunction "C_3") (pintype "passive"))
      (node (ref "R8") (pin "1") (pinfunction "1_1") (pintype "passive"))
    )
    (net (code "52") (name "Net-(Q10-B)") (class "Default")
      (node (ref "Q10") (pin "2") (pinfunction "B_2") (pintype "passive"))
      (node (ref "R9") (pin "1") (pinfunction "1_1") (pintype "passive"))
    )
    (net (code "53") (name "Net-(Q10-C)") (class "Default")
      (node (ref "Q10") (pin "3") (pinfunction "C_3") (pintype "passive"))
      (node (ref "Q12") (pin "2") (pinfunction "B_2") (pintype "passive"))
    )
    (net (code "54") (name "Net-(Q11-B)") (class "Default")
      (node (ref "Q11") (pin "2") (pinfunction "B_2") (pintype "passive"))
      (node (ref "R10") (pin "1") (pinfunction "1_1") (pintype "passive"))
    )
    (net (code "55") (name "Net-(Q11-C)") (class "Default")
      (node (ref "Q11") (pin "3") (pinfunction "C_3") (pintype "passive"))
      (node (ref "Q13") (pin "2") (pinfunction "B_2") (pintype "passive"))
    )
    (net (code "56") (name "Net-(Q12-C)") (class "Default")
      (node (ref "Q12") (pin "3") (pinfunction "C_3") (pintype "passive"))
      (node (ref "Q13") (pin "3") (pinfunction "C_3") (pintype "passive"))
      (node (ref "Q14") (pin "2") (pinfunction "B_2") (pintype "passive"))
      (node (ref "R11") (pin "1") (pinfunction "1_1") (pintype "passive"))
    )
    (net (code "57") (name "Net-(Q12-E)") (class "Default")
      (node (ref "Q12") (pin "1") (pinfunction "E_1") (pintype "passive"))
      (node (ref "Q13") (pin "1") (pinfunction "E_1") (pintype "passive"))
      (node (ref "Q15") (pin "2") (pinfunction "B_2") (pintype "passive"))
      (node (ref "R12") (pin "2") (pinfunction "2_2") (pintype "passive"))
    )
    (net (code "58") (name "Net-(Q14-C)") (class "Default")
      (node (ref "Q14") (pin "3") (pinfunction "C_3") (pintype "passive"))
      (node (ref "R13") (pin "1") (pinfunction "1_1") (pintype "passive"))
    )
    (net (code "59") (name "Net-(Q16-C)") (class "Default")
      (node (ref "Q16") (pin "3") (pinfunction "C_3") (pintype "passive"))
      (node (ref "Q19") (pin "2") (pinfunction "B_2") (pintype "passive"))
    )
    (net (code "60") (name "Net-(Q18-B)") (class "Default")
      (node (ref "Q18") (pin "2") (pinfunction "B_2") (pintype "passive"))
      (node (ref "R106") (pin "1") (pinfunction "1_1") (pintype "passive"))
    )
    (net (code "61") (name "Net-(Q19-E)") (class "Default")
      (node (ref "Q19") (pin "1") (pinfunction "E_1") (pintype "passive"))
      (node (ref "Q21") (pin "2") (pinfunction "B_2") (pintype "passive"))
      (node (ref "R17") (pin "2") (pinfunction "2_2") (pintype "passive"))
    )
    (net (code "62") (name "Net-(Q20-C)") (class "Default")
      (node (ref "Q20") (pin "3") (pinfunction "C_3") (pintype "passive"))
      (node (ref "R18") (pin "1") (pinfunction "1_1") (pintype "passive"))
    )
    (net (code "63") (name "Net-(Q23-D)") (class "Default")
      (node (ref "O5") (pin "3") (pinfunction "3_3") (pintype "passive"))
      (node (ref "OC_NOT") (pin "1") (pinfunction "1_1") (pintype "passive"))
      (node (ref "OC_NOT") (pin "2") (pinfunction "2_2") (pintype "passive"))
      (node (ref "Q23") (pin "1") (pinfunction "D_1") (pintype "passive"))
      (node (ref "Q24") (pin "1") (pinfunction "D_1") (pintype "passive"))
    )
    (net (code "64") (name "Net-(Q23-G)") (class "Default")
      (node (ref "IC_NOT") (pin "1") (pinfunction "1_1") (pintype "passive"))
      (node (ref "IC_NOT") (pin "2") (pinfunction "2_2") (pintype "passive"))
      (node (ref "In_13") (pin "2") (pinfunction "2_2") (pintype "passive"))
      (node (ref "Q23") (pin "2") (pinfunction "G_2") (pintype "passive"))
      (node (ref "Q24") (pin "2") (pinfunction "G_2") (pintype "passive"))
    )
    (net (code "65") (name "Net-(Q23-S)") (class "Default")
      (node (ref "O7") (pin "2") (pinfunction "2_2") (pintype "passive"))
      (node (ref "Q23") (pin "3") (pinfunction "S_3") (pintype "passive"))
      (node (ref "Vcc5") (pin "3") (pinfunction "3_3") (pintype "passive"))
    )
    (net (code "66") (name "Net-(Q25-D)") (class "Default")
      (node (ref "O7") (pin "3") (pinfunction "3_3") (pintype "passive"))
      (node (ref "OC_NAND") (pin "1") (pinfunction "1_1") (pintype "passive"))
      (node (ref "OC_NAND") (pin "2") (pinfunction "2_2") (pintype "passive"))
      (node (ref "Q25") (pin "1") (pinfunction "D_1") (pintype "passive"))
      (node (ref "Q26") (pin "1") (pinfunction "D_1") (pintype "passive"))
      (node (ref "Q27") (pin "1") (pinfunction "D_1") (pintype "passive"))
    )
    (net (code "67") (name "Net-(Q25-G)") (class "Default")
      (node (ref "In_12") (pin "2") (pinfunction "2_2") (pintype "passive"))
      (node (ref "Q25") (pin "2") (pinfunction "G_2") (pintype "passive"))
      (node (ref "Q27") (pin "2") (pinfunction "G_2") (pintype "passive"))
    )
    (net (code "68") (name "Net-(Q25-S)") (class "Default")
      (node (ref "Q25") (pin "3") (pinfunction "S_3") (pintype "passive"))
      (node (ref "Q26") (pin "3") (pinfunction "S_3") (pintype "passive"))
      (node (ref "Vcc7") (pin "3") (pinfunction "3_3") (pintype "passive"))
    )
    (net (code "69") (name "Net-(Q26-G)") (class "Default")
      (node (ref "In_11") (pin "2") (pinfunction "2_2") (pintype "passive"))
      (node (ref "Q26") (pin "2") (pinfunction "G_2") (pintype "passive"))
      (node (ref "Q28") (pin "2") (pinfunction "G_2") (pintype "passive"))
    )
    (net (code "70") (name "Net-(Q27-S)") (class "Default")
      (node (ref "Q27") (pin "3") (pinfunction "S_3") (pintype "passive"))
      (node (ref "Q28") (pin "1") (pinfunction "D_1") (pintype "passive"))
    )
    (net (code "71") (name "Net-(Q29-D)") (class "Default")
      (node (ref "Q29") (pin "1") (pinfunction "D_1") (pintype "passive"))
      (node (ref "Q30") (pin "3") (pinfunction "S_3") (pintype "passive"))
    )
    (net (code "72") (name "Net-(Q29-G)") (class "Default")
      (node (ref "In_15") (pin "2") (pinfunction "2_2") (pintype "passive"))
      (node (ref "Q29") (pin "2") (pinfunction "G_2") (pintype "passive"))
      (node (ref "Q31") (pin "2") (pinfunction "G_2") (pintype "passive"))
    )
    (net (code "73") (name "Net-(Q29-S)") (class "Default")
      (node (ref "O6") (pin "2") (pinfunction "2_2") (pintype "passive"))
      (node (ref "Q29") (pin "3") (pinfunction "S_3") (pintype "passive"))
      (node (ref "Vcc6") (pin "3") (pinfunction "3_3") (pintype "passive"))
    )
    (net (code "74") (name "Net-(Q30-D)") (class "Default")
      (node (ref "O6") (pin "3") (pinfunction "3_3") (pintype "passive"))
      (node (ref "OC_NOR") (pin "1") (pinfunction "1_1") (pintype "passive"))
      (node (ref "OC_NOR") (pin "2") (pinfunction "2_2") (pintype "passive"))
      (node (ref "Q30") (pin "1") (pinfunction "D_1") (pintype "passive"))
      (node (ref "Q31") (pin "1") (pinfunction "D_1") (pintype "passive"))
      (node (ref "Q32") (pin "1") (pinfunction "D_1") (pintype "passive"))
    )
    (net (code "75") (name "Net-(Q30-G)") (class "Default")
      (node (ref "In_14") (pin "2") (pinfunction "2_2") (pintype "passive"))
      (node (ref "Q30") (pin "2") (pinfunction "G_2") (pintype "passive"))
      (node (ref "Q32") (pin "2") (pinfunction "G_2") (pintype "passive"))
    )
    (net (code "76") (name "Net-(Q33-D)") (class "Default")
      (node (ref "Q33") (pin "1") (pinfunction "D_1") (pintype "passive"))
      (node (ref "Q34") (pin "1") (pinfunction "D_1") (pintype "passive"))
      (node (ref "Q38") (pin "2") (pinfunction "G_2") (pintype "passive"))
    )
    (net (code "77") (name "Net-(Q33-G)") (class "Default")
      (node (ref "In_16") (pin "2") (pinfunction "2_2") (pintype "passive"))
      (node (ref "Q33") (pin "2") (pinfunction "G_2") (pintype "passive"))
      (node (ref "Q34") (pin "2") (pinfunction "G_2") (pintype "passive"))
      (node (ref "Q35") (pin "2") (pinfunction "G_2") (pintype "passive"))
    )
    (net (code "78") (name "Net-(Q33-S)") (class "Default")
      (node (ref "O8") (pin "2") (pinfunction "2_2") (pintype "passive"))
      (node (ref "Q33") (pin "3") (pinfunction "S_3") (pintype "passive"))
      (node (ref "Q35") (pin "3") (pinfunction "S_3") (pintype "passive"))
      (node (ref "Vcc8") (pin "3") (pinfunction "3_3") (pintype "passive"))
    )
    (net (code "79") (name "Net-(Q35-D)") (class "Default")
      (node (ref "Q35") (pin "1") (pinfunction "D_1") (pintype "passive"))
      (node (ref "Q36") (pin "3") (pinfunction "S_3") (pintype "passive"))
    )
    (net (code "80") (name "Net-(Q36-D)") (class "Default")
      (node (ref "O8") (pin "3") (pinfunction "3_3") (pintype "passive"))
      (node (ref "Q36") (pin "1") (pinfunction "D_1") (pintype "passive"))
      (node (ref "Q37") (pin "1") (pinfunction "D_1") (pintype "passive"))
    )
    (net (code "81") (name "Net-(Q36-G)") (class "Default")
      (node (ref "In_17") (pin "2") (pinfunction "2_2") (pintype "passive"))
      (node (ref "Q36") (pin "2") (pinfunction "G_2") (pintype "passive"))
      (node (ref "Q37") (pin "2") (pinfunction "G_2") (pintype "passive"))
    )
    (net (code "82") (name "Net-(Q37-S)") (class "Default")
      (node (ref "Q37") (pin "3") (pinfunction "S_3") (pintype "passive"))
      (node (ref "Q38") (pin "1") (pinfunction "D_1") (pintype "passive"))
    )
    (net (code "83") (name "Net-(R1-Pad2)") (class "Default")
      (node (ref "R1") (pin "2") (pinfunction "2_2") (pintype "passive"))
      (node (ref "R2") (pin "2") (pinfunction "2_2") (pintype "passive"))
      (node (ref "R4") (pin "2") (pinfunction "2_2") (pintype "passive"))
      (node (ref "Vcc1") (pin "3") (pinfunction "3_3") (pintype "passive"))
    )
    (net (code "84") (name "Net-(R5-Pad2)") (class "Default")
      (node (ref "R5") (pin "2") (pinfunction "2_2") (pintype "passive"))
      (node (ref "R6") (pin "2") (pinfunction "2_2") (pintype "passive"))
      (node (ref "R8") (pin "2") (pinfunction "2_2") (pintype "passive"))
      (node (ref "Vcc2") (pin "2") (pinfunction "2_2") (pintype "passive"))
    )
    (net (code "85") (name "Net-(R10-Pad2)") (class "Default")
      (node (ref "R10") (pin "2") (pinfunction "2_2") (pintype "passive"))
      (node (ref "R11") (pin "2") (pinfunction "2_2") (pintype "passive"))
      (node (ref "R13") (pin "2") (pinfunction "2_2") (pintype "passive"))
      (node (ref "R9") (pin "2") (pinfunction "2_2") (pintype "passive"))
      (node (ref "Vcc3") (pin "3") (pinfunction "3_3") (pintype "passive"))
    )
    (net (code "86") (name "Net-(R14-Pad2)") (class "Default")
      (node (ref "R14") (pin "2") (pinfunction "2_2") (pintype "passive"))
      (node (ref "R15") (pin "2") (pinfunction "2_2") (pintype "passive"))
      (node (ref "R16") (pin "2") (pinfunction "2_2") (pintype "passive"))
      (node (ref "R18") (pin "2") (pinfunction "2_2") (pintype "passive"))
      (node (ref "Vcc4") (pin "3") (pinfunction "3_3") (pintype "passive"))
    )
    (net (code "87") (name "VCC00") (class "Default")
      (node (ref "PS00") (pin "2") (pinfunction "2_2") (pintype "passive"))
      (node (ref "R_in00") (pin "1") (pinfunction "1_1") (pintype "passive"))
      (node (ref "R_in01") (pin "1") (pinfunction "1_1") (pintype "passive"))
      (node (ref "R_in02") (pin "1") (pinfunction "1_1") (pintype "passive"))
      (node (ref "R_in03") (pin "1") (pinfunction "1_1") (pintype "passive"))
      (node (ref "R_in04") (pin "1") (pinfunction "1_1") (pintype "passive"))
      (node (ref "R_in05") (pin "1") (pinfunction "1_1") (pintype "passive"))
      (node (ref "R_in06") (pin "1") (pinfunction "1_1") (pintype "passive"))
      (node (ref "Vcc1") (pin "1") (pinfunction "1_1") (pintype "passive"))
      (node (ref "Vcc2") (pin "1") (pinfunction "1_1") (pintype "passive"))
      (node (ref "Vcc3") (pin "1") (pinfunction "1_1") (pintype "passive"))
      (node (ref "Vcc4") (pin "1") (pinfunction "1_1") (pintype "passive"))
    )
    (net (code "88") (name "VCC01") (class "Default")
      (node (ref "PS01") (pin "2") (pinfunction "2_2") (pintype "passive"))
      (node (ref "R_in10") (pin "1") (pinfunction "1_1") (pintype "passive"))
      (node (ref "R_in11") (pin "1") (pinfunction "1_1") (pintype "passive"))
      (node (ref "R_in12") (pin "1") (pinfunction "1_1") (pintype "passive"))
      (node (ref "R_in13") (pin "1") (pinfunction "1_1") (pintype "passive"))
      (node (ref "R_in14") (pin "1") (pinfunction "1_1") (pintype "passive"))
      (node (ref "R_in15") (pin "1") (pinfunction "1_1") (pintype "passive"))
      (node (ref "R_in16") (pin "1") (pinfunction "1_1") (pintype "passive"))
      (node (ref "Vcc5") (pin "1") (pinfunction "1_1") (pintype "passive"))
      (node (ref "Vcc6") (pin "1") (pinfunction "1_1") (pintype "passive"))
      (node (ref "Vcc7") (pin "1") (pinfunction "1_1") (pintype "passive"))
      (node (ref "Vcc8") (pin "1") (pinfunction "1_1") (pintype "passive"))
    )
    (net (code "89") (name "unconnected-(O5-Pad2)") (class "Default")
      (node (ref "O5") (pin "2") (pinfunction "2_2") (pintype "passive"))
    )
  )
)
